# HackmodWear_workingcopy3.net
KiCad netlist of a schematic drawn in EAGLE
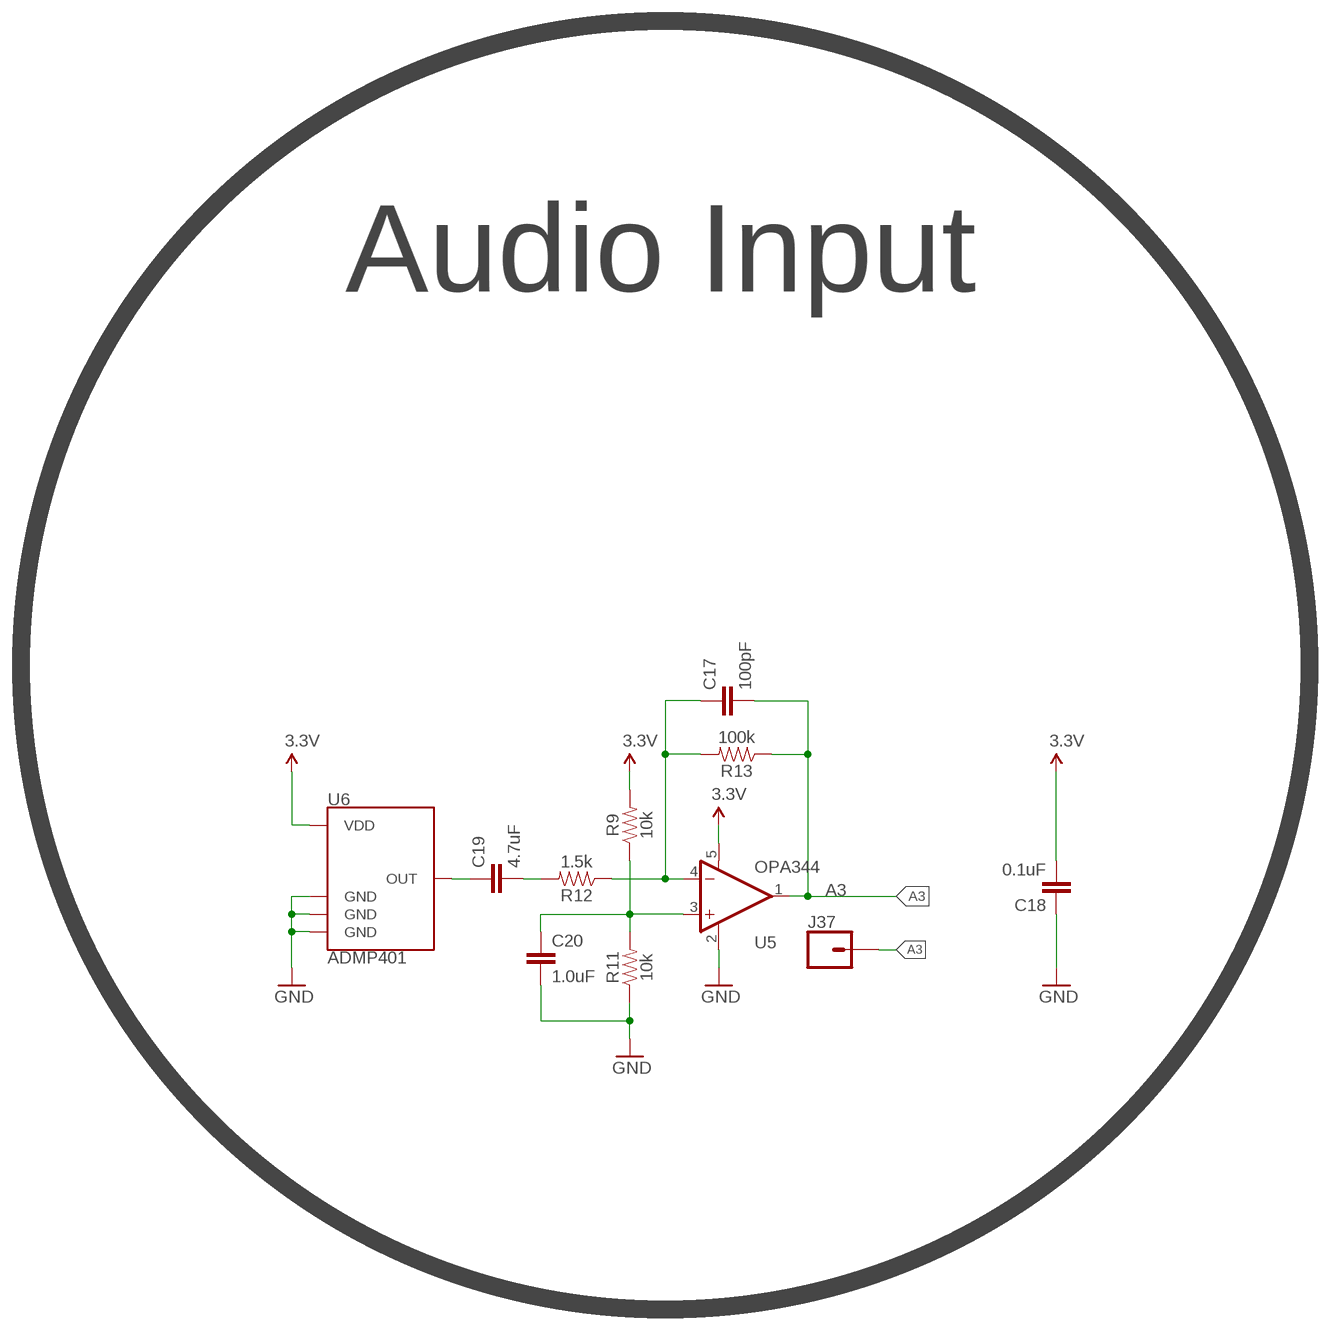
[diagram p0: schematic, sheet 1, part 1 of 3]
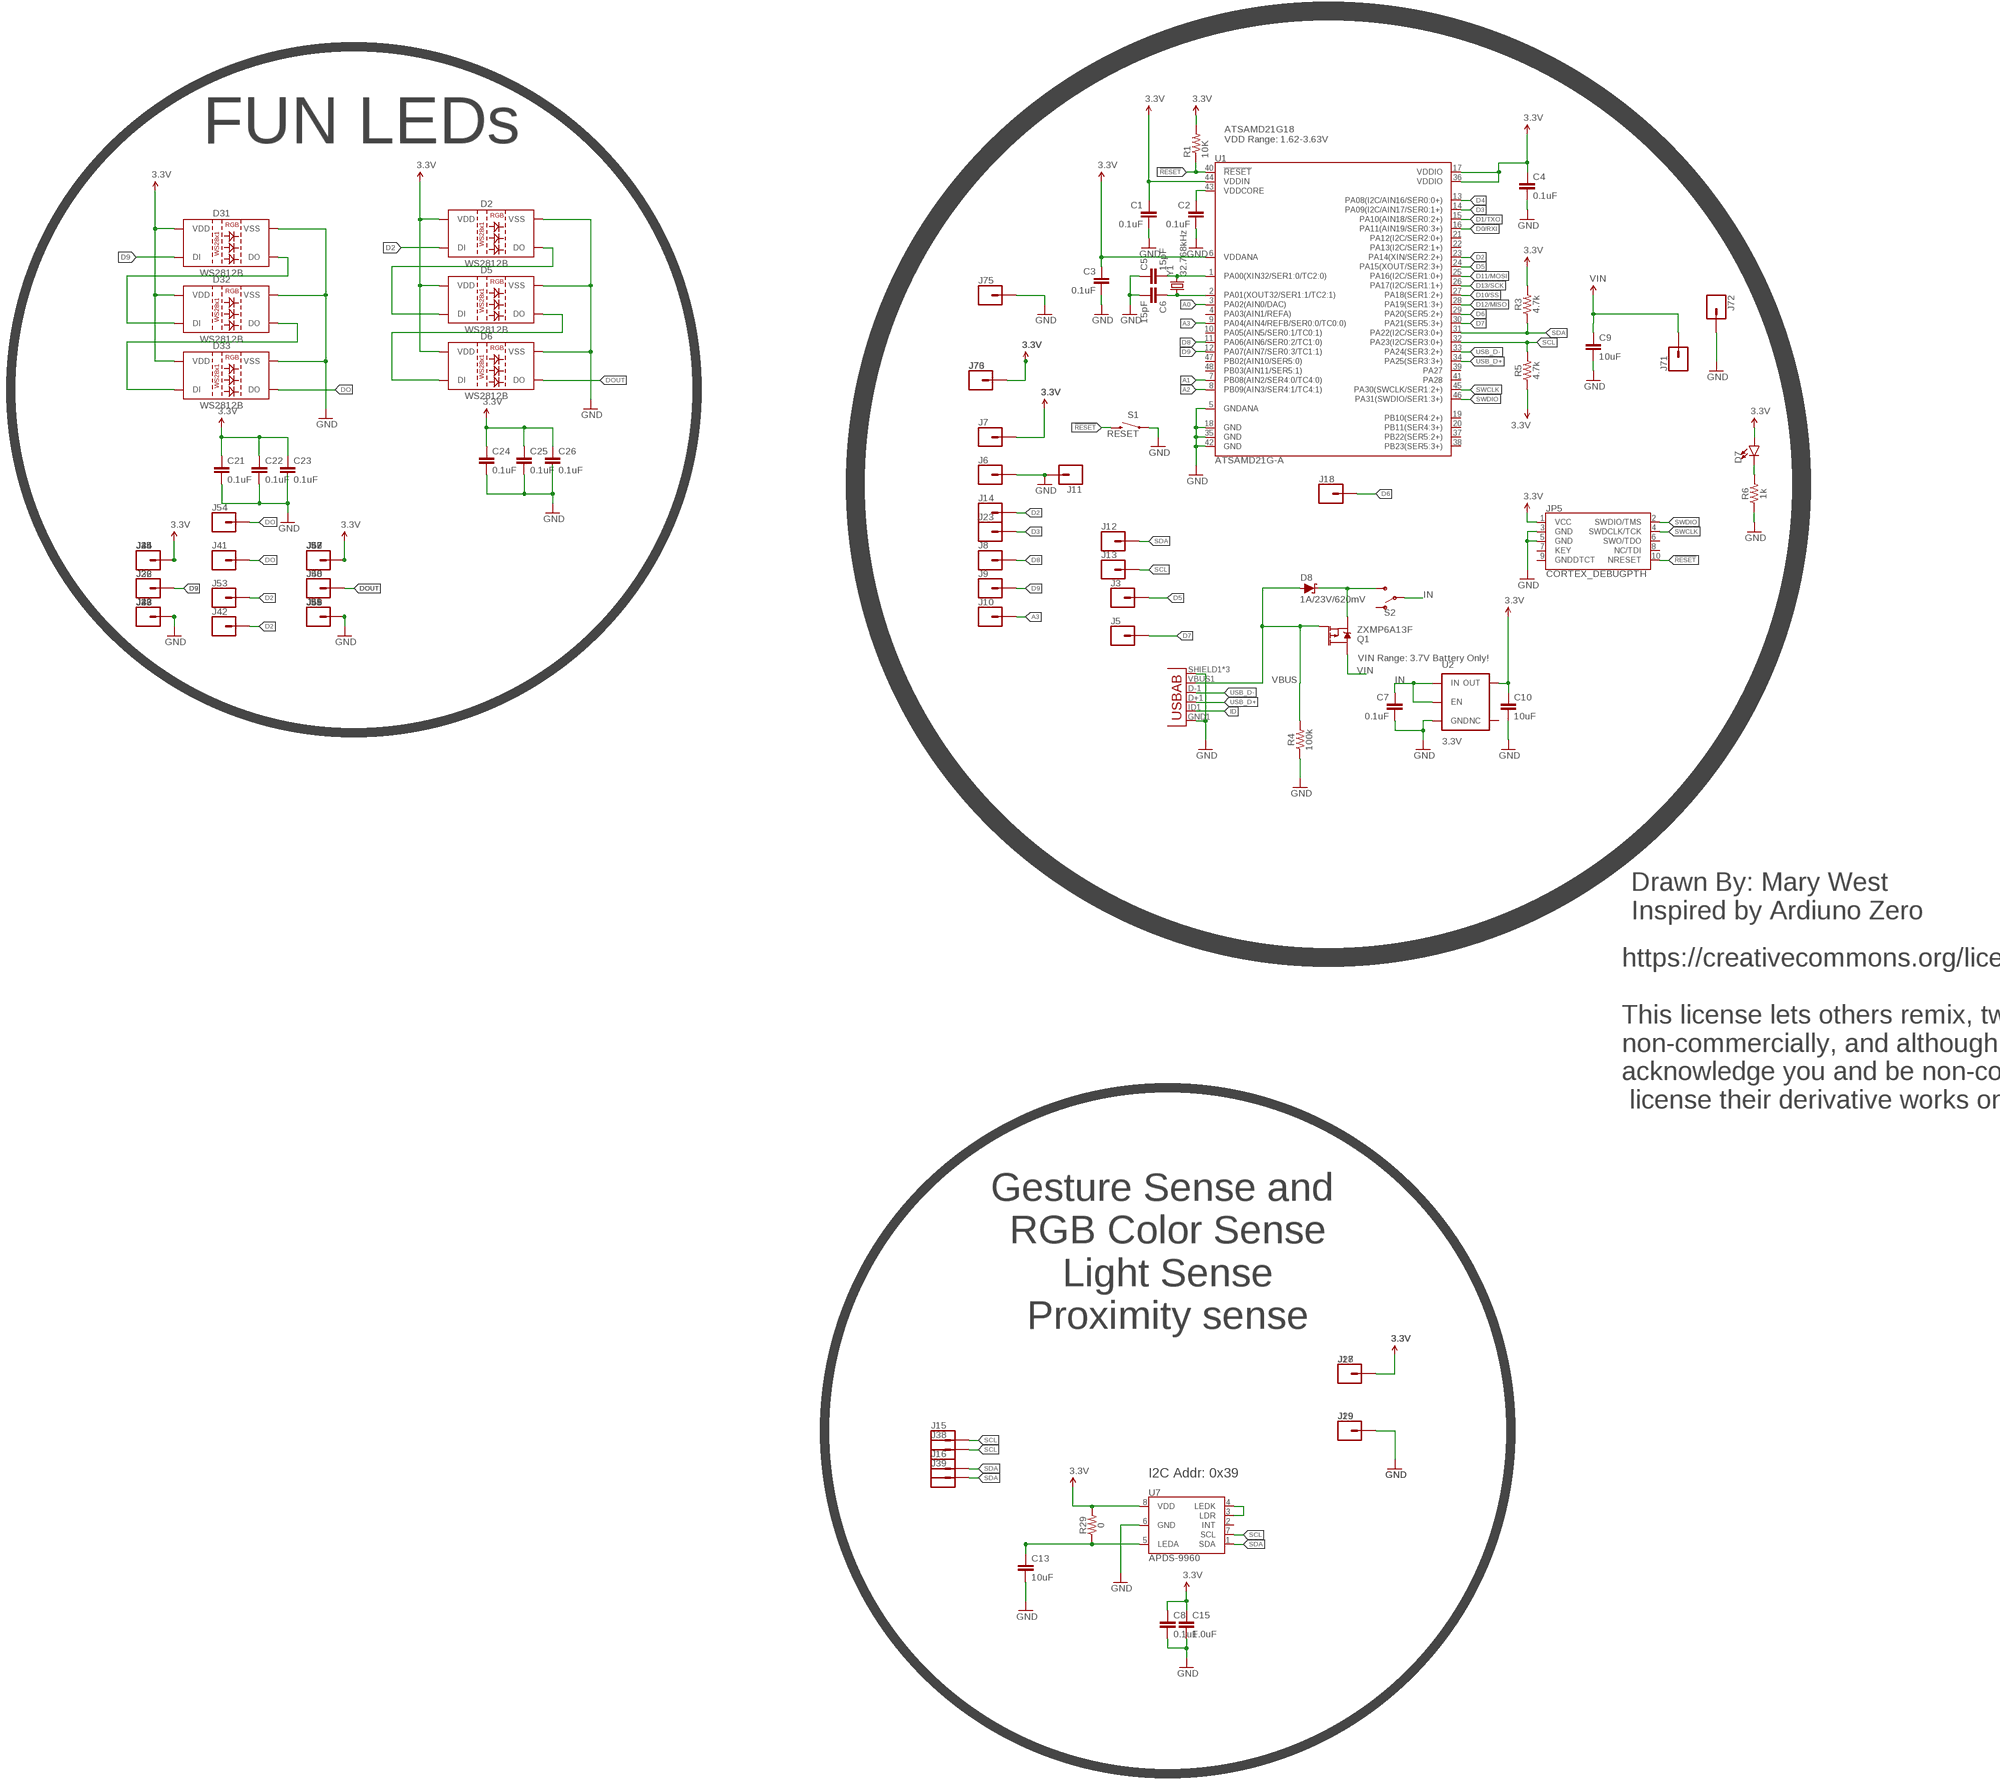
[diagram p1: schematic, sheet 1, part 2 of 3]
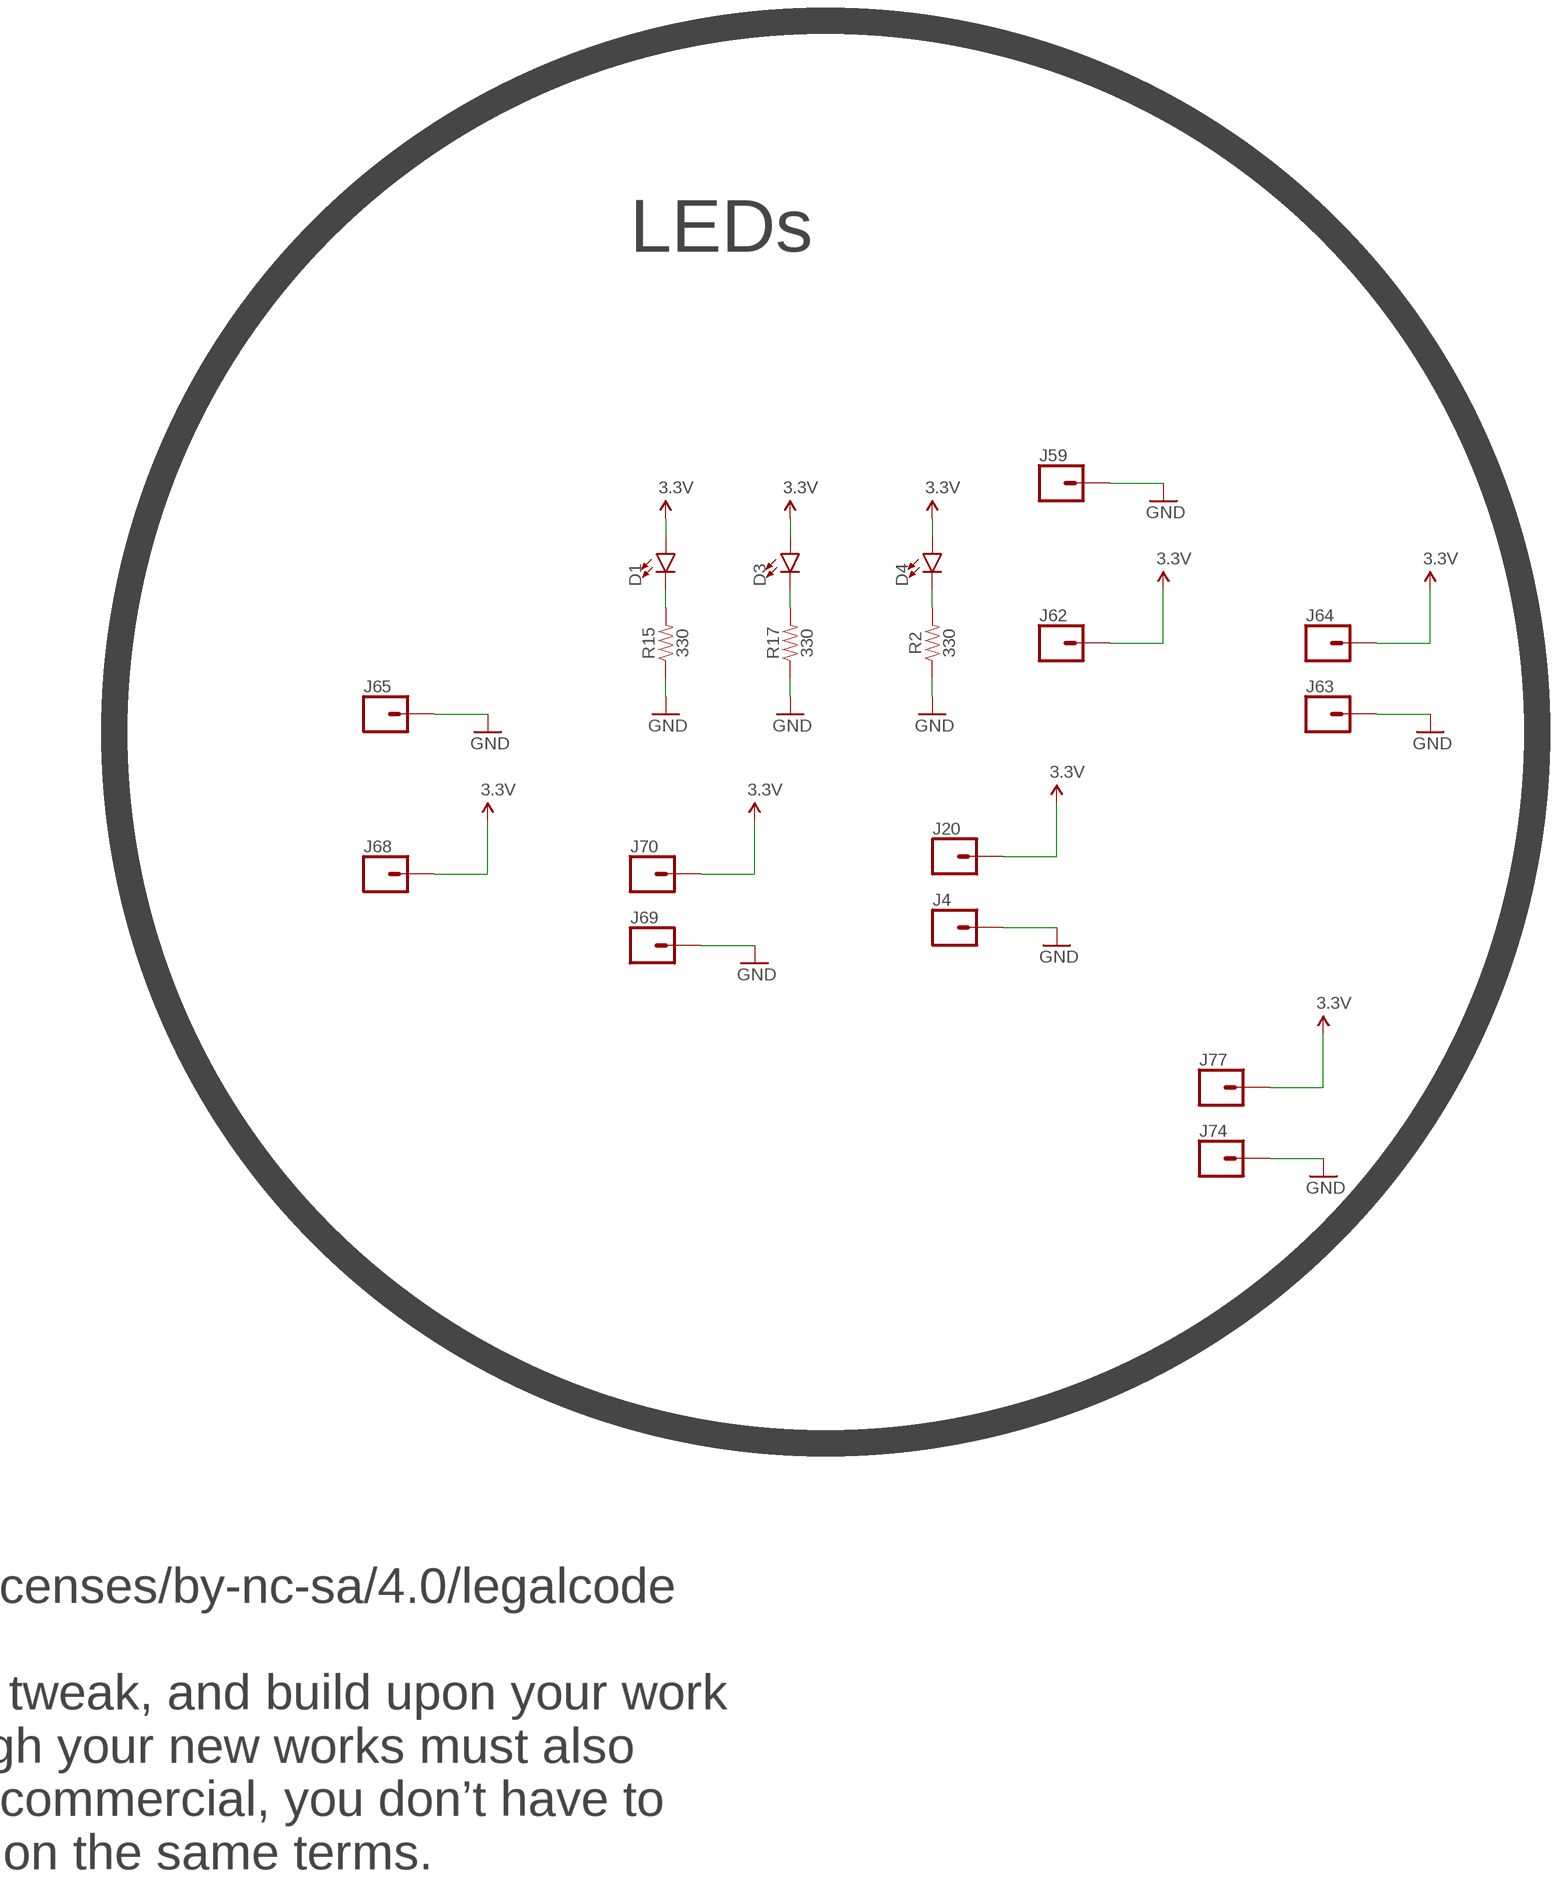
[diagram p2: schematic, sheet 1, part 3 of 3]

(export (version "E")
  (design (tool "Eeschema 10.0.6"))
  (components
    (comp (ref "C1")
      (value "0.1uF")
      (footprint "eagle-import:0603")
      (libsource (lib "eagle-import") (part "0.1UF-0603-25V-(+80/-20%)"))
    )
    (comp (ref "C2")
      (value "0.1uF")
      (footprint "eagle-import:0603")
      (libsource (lib "eagle-import") (part "0.1UF-0603-25V-(+80/-20%)"))
    )
    (comp (ref "C3")
      (value "0.1uF")
      (footprint "eagle-import:0603")
      (libsource (lib "eagle-import") (part "0.1UF-0603-25V-(+80/-20%)"))
    )
    (comp (ref "C4")
      (value "0.1uF")
      (footprint "eagle-import:0603")
      (libsource (lib "eagle-import") (part "0.1UF-0603-25V-(+80/-20%)"))
    )
    (comp (ref "C5")
      (value "15pF")
      (footprint "eagle-import:0603")
      (libsource (lib "eagle-import") (part "15PF-0603-50V-5%"))
    )
    (comp (ref "C6")
      (value "15pF")
      (footprint "eagle-import:0603")
      (libsource (lib "eagle-import") (part "15PF-0603-50V-5%"))
    )
    (comp (ref "C7")
      (value "0.1uF")
      (footprint "eagle-import:0603")
      (libsource (lib "eagle-import") (part "0.1UF-0603-25V-(+80/-20%)"))
    )
    (comp (ref "C8")
      (value "0.1uF")
      (footprint "eagle-import:0603")
      (libsource (lib "eagle-import") (part "0.1UF-0603-25V-(+80/-20%)"))
    )
    (comp (ref "C9")
      (value "10uF")
      (footprint "eagle-import:0603")
      (libsource (lib "eagle-import") (part "SparkFun-Capacitors_510_10UF-0603-6.3V-20%"))
    )
    (comp (ref "C10")
      (value "10uF")
      (footprint "eagle-import:0603")
      (libsource (lib "eagle-import") (part "SparkFun-Capacitors_510_10UF-0603-6.3V-20%"))
    )
    (comp (ref "C13")
      (value "10uF")
      (footprint "eagle-import:0805")
      (libsource (lib "eagle-import") (part "10UF-0805-10V-10%"))
    )
    (comp (ref "C15")
      (value "1.0uF")
      (footprint "eagle-import:0603")
      (libsource (lib "eagle-import") (part "1.0UF-0603-16V-10%"))
    )
    (comp (ref "C17")
      (value "100pF")
      (footprint "eagle-import:0603")
      (libsource (lib "eagle-import") (part "100PF-0603-50V-5%"))
    )
    (comp (ref "C18")
      (value "0.1uF")
      (footprint "eagle-import:0603")
      (libsource (lib "eagle-import") (part "0.1UF-0603-25V-(+80/-20%)"))
    )
    (comp (ref "C19")
      (value "4.7uF")
      (footprint "eagle-import:0603")
      (libsource (lib "eagle-import") (part "4.7UF-0603-6.3V-(10%)"))
    )
    (comp (ref "C20")
      (value "1.0uF")
      (footprint "eagle-import:0603")
      (libsource (lib "eagle-import") (part "1.0UF-0603-16V-10%"))
    )
    (comp (ref "C21")
      (value "0.1uF")
      (footprint "eagle-import:0603")
      (libsource (lib "eagle-import") (part "0.1UF-0603-25V-(+80/-20%)"))
    )
    (comp (ref "C22")
      (value "0.1uF")
      (footprint "eagle-import:0603")
      (libsource (lib "eagle-import") (part "0.1UF-0603-25V-(+80/-20%)"))
    )
    (comp (ref "C23")
      (value "0.1uF")
      (footprint "eagle-import:0603")
      (libsource (lib "eagle-import") (part "0.1UF-0603-25V-(+80/-20%)"))
    )
    (comp (ref "C24")
      (value "0.1uF")
      (footprint "eagle-import:0603")
      (libsource (lib "eagle-import") (part "0.1UF-0603-25V-(+80/-20%)"))
    )
    (comp (ref "C25")
      (value "0.1uF")
      (footprint "eagle-import:0603")
      (libsource (lib "eagle-import") (part "0.1UF-0603-25V-(+80/-20%)"))
    )
    (comp (ref "C26")
      (value "0.1uF")
      (footprint "eagle-import:0603")
      (libsource (lib "eagle-import") (part "0.1UF-0603-25V-(+80/-20%)"))
    )
    (comp (ref "D1")
      (value "LED1206")
      (footprint "eagle-import:LED-1206")
      (libsource (lib "eagle-import") (part "LED1206"))
    )
    (comp (ref "D2")
      (value "WS2812B")
      (footprint "eagle-import:WS2812B")
      (libsource (lib "eagle-import") (part "WS2812B"))
    )
    (comp (ref "D3")
      (value "LED1206")
      (footprint "eagle-import:LED-1206")
      (libsource (lib "eagle-import") (part "LED1206"))
    )
    (comp (ref "D4")
      (value "LED1206")
      (footprint "eagle-import:LED-1206")
      (libsource (lib "eagle-import") (part "LED1206"))
    )
    (comp (ref "D5")
      (value "WS2812B")
      (footprint "eagle-import:WS2812B")
      (libsource (lib "eagle-import") (part "WS2812B"))
    )
    (comp (ref "D6")
      (value "WS2812B")
      (footprint "eagle-import:WS2812B")
      (libsource (lib "eagle-import") (part "WS2812B"))
    )
    (comp (ref "D7")
      (value "LED1206")
      (footprint "eagle-import:LED-1206")
      (libsource (lib "eagle-import") (part "LED1206"))
    )
    (comp (ref "D8")
      (value "1A/23V/620mV")
      (footprint "eagle-import:SOD-323")
      (libsource (lib "eagle-import") (part "DIODE-SCHOTTKY-BAT20J"))
    )
    (comp (ref "D31")
      (value "WS2812B")
      (footprint "eagle-import:WS2812B")
      (libsource (lib "eagle-import") (part "WS2812B"))
    )
    (comp (ref "D32")
      (value "WS2812B")
      (footprint "eagle-import:WS2812B")
      (libsource (lib "eagle-import") (part "WS2812B"))
    )
    (comp (ref "D33")
      (value "WS2812B")
      (footprint "eagle-import:WS2812B")
      (libsource (lib "eagle-import") (part "WS2812B"))
    )
    (comp (ref "J3")
      (value "CONN_01")
      (footprint "eagle-import:1X01")
      (libsource (lib "eagle-import") (part "CONN_01"))
    )
    (comp (ref "J4")
      (value "CONN_01")
      (footprint "eagle-import:1X01")
      (libsource (lib "eagle-import") (part "CONN_01"))
    )
    (comp (ref "J5")
      (value "CONN_01")
      (footprint "eagle-import:1X01")
      (libsource (lib "eagle-import") (part "CONN_01"))
    )
    (comp (ref "J6")
      (value "CONN_01")
      (footprint "eagle-import:1X01")
      (libsource (lib "eagle-import") (part "CONN_01"))
    )
    (comp (ref "J7")
      (value "CONN_01")
      (footprint "eagle-import:1X01")
      (libsource (lib "eagle-import") (part "CONN_01"))
    )
    (comp (ref "J8")
      (value "CONN_01")
      (footprint "eagle-import:1X01")
      (libsource (lib "eagle-import") (part "CONN_01"))
    )
    (comp (ref "J9")
      (value "CONN_01")
      (footprint "eagle-import:1X01")
      (libsource (lib "eagle-import") (part "CONN_01"))
    )
    (comp (ref "J10")
      (value "CONN_01")
      (footprint "eagle-import:1X01")
      (libsource (lib "eagle-import") (part "CONN_01"))
    )
    (comp (ref "J11")
      (value "CONN_01")
      (footprint "eagle-import:1X01")
      (libsource (lib "eagle-import") (part "CONN_01"))
    )
    (comp (ref "J12")
      (value "CONN_01")
      (footprint "eagle-import:1X01")
      (libsource (lib "eagle-import") (part "CONN_01"))
    )
    (comp (ref "J13")
      (value "CONN_01")
      (footprint "eagle-import:1X01")
      (libsource (lib "eagle-import") (part "CONN_01"))
    )
    (comp (ref "J14")
      (value "CONN_01")
      (footprint "eagle-import:1X01")
      (libsource (lib "eagle-import") (part "CONN_01"))
    )
    (comp (ref "J15")
      (value "CONN_01")
      (footprint "eagle-import:1X01")
      (libsource (lib "eagle-import") (part "CONN_01"))
    )
    (comp (ref "J16")
      (value "CONN_01")
      (footprint "eagle-import:1X01")
      (libsource (lib "eagle-import") (part "CONN_01"))
    )
    (comp (ref "J17")
      (value "CONN_01")
      (footprint "eagle-import:1X01")
      (libsource (lib "eagle-import") (part "CONN_01"))
    )
    (comp (ref "J18")
      (value "CONN_01")
      (footprint "eagle-import:1X01")
      (libsource (lib "eagle-import") (part "CONN_01"))
    )
    (comp (ref "J19")
      (value "CONN_01")
      (footprint "eagle-import:1X01")
      (libsource (lib "eagle-import") (part "CONN_01"))
    )
    (comp (ref "J20")
      (value "CONN_01")
      (footprint "eagle-import:1X01")
      (libsource (lib "eagle-import") (part "CONN_01"))
    )
    (comp (ref "J23")
      (value "CONN_01")
      (footprint "eagle-import:1X01")
      (libsource (lib "eagle-import") (part "CONN_01"))
    )
    (comp (ref "J25")
      (value "CONN_01")
      (footprint "eagle-import:1X01")
      (libsource (lib "eagle-import") (part "CONN_01"))
    )
    (comp (ref "J26")
      (value "CONN_01")
      (footprint "eagle-import:1X01")
      (libsource (lib "eagle-import") (part "CONN_01"))
    )
    (comp (ref "J27")
      (value "CONN_01")
      (footprint "eagle-import:1X01")
      (libsource (lib "eagle-import") (part "CONN_01"))
    )
    (comp (ref "J28")
      (value "CONN_01")
      (footprint "eagle-import:1X01")
      (libsource (lib "eagle-import") (part "CONN_01"))
    )
    (comp (ref "J29")
      (value "CONN_01")
      (footprint "eagle-import:1X01")
      (libsource (lib "eagle-import") (part "CONN_01"))
    )
    (comp (ref "J32")
      (value "CONN_01")
      (footprint "eagle-import:1X01")
      (libsource (lib "eagle-import") (part "CONN_01"))
    )
    (comp (ref "J33")
      (value "CONN_01")
      (footprint "eagle-import:1X01")
      (libsource (lib "eagle-import") (part "CONN_01"))
    )
    (comp (ref "J34")
      (value "CONN_01")
      (footprint "eagle-import:1X01")
      (libsource (lib "eagle-import") (part "CONN_01"))
    )
    (comp (ref "J37")
      (value "CONN_01")
      (footprint "eagle-import:1X01")
      (libsource (lib "eagle-import") (part "CONN_01"))
    )
    (comp (ref "J38")
      (value "CONN_01")
      (footprint "eagle-import:1X01")
      (libsource (lib "eagle-import") (part "CONN_01"))
    )
    (comp (ref "J39")
      (value "CONN_01")
      (footprint "eagle-import:1X01")
      (libsource (lib "eagle-import") (part "CONN_01"))
    )
    (comp (ref "J41")
      (value "CONN_01")
      (footprint "eagle-import:1X01")
      (libsource (lib "eagle-import") (part "CONN_01"))
    )
    (comp (ref "J42")
      (value "CONN_01")
      (footprint "eagle-import:1X01")
      (libsource (lib "eagle-import") (part "CONN_01"))
    )
    (comp (ref "J43")
      (value "CONN_01")
      (footprint "eagle-import:1X01")
      (libsource (lib "eagle-import") (part "CONN_01"))
    )
    (comp (ref "J44")
      (value "CONN_01")
      (footprint "eagle-import:1X01")
      (libsource (lib "eagle-import") (part "CONN_01"))
    )
    (comp (ref "J45")
      (value "CONN_01")
      (footprint "eagle-import:1X01")
      (libsource (lib "eagle-import") (part "CONN_01"))
    )
    (comp (ref "J46")
      (value "CONN_01")
      (footprint "eagle-import:1X01")
      (libsource (lib "eagle-import") (part "CONN_01"))
    )
    (comp (ref "J47")
      (value "CONN_01")
      (footprint "eagle-import:1X01")
      (libsource (lib "eagle-import") (part "CONN_01"))
    )
    (comp (ref "J48")
      (value "CONN_01")
      (footprint "eagle-import:1X01")
      (libsource (lib "eagle-import") (part "CONN_01"))
    )
    (comp (ref "J49")
      (value "CONN_01")
      (footprint "eagle-import:1X01")
      (libsource (lib "eagle-import") (part "CONN_01"))
    )
    (comp (ref "J50")
      (value "CONN_01")
      (footprint "eagle-import:1X01")
      (libsource (lib "eagle-import") (part "CONN_01"))
    )
    (comp (ref "J51")
      (value "CONN_01")
      (footprint "eagle-import:1X01")
      (libsource (lib "eagle-import") (part "CONN_01"))
    )
    (comp (ref "J52")
      (value "CONN_01")
      (footprint "eagle-import:1X01")
      (libsource (lib "eagle-import") (part "CONN_01"))
    )
    (comp (ref "J53")
      (value "CONN_01")
      (footprint "eagle-import:1X01")
      (libsource (lib "eagle-import") (part "CONN_01"))
    )
    (comp (ref "J54")
      (value "CONN_01")
      (footprint "eagle-import:1X01")
      (libsource (lib "eagle-import") (part "CONN_01"))
    )
    (comp (ref "J55")
      (value "CONN_01")
      (footprint "eagle-import:1X01")
      (libsource (lib "eagle-import") (part "CONN_01"))
    )
    (comp (ref "J56")
      (value "CONN_01")
      (footprint "eagle-import:1X01")
      (libsource (lib "eagle-import") (part "CONN_01"))
    )
    (comp (ref "J57")
      (value "CONN_01")
      (footprint "eagle-import:1X01")
      (libsource (lib "eagle-import") (part "CONN_01"))
    )
    (comp (ref "J58")
      (value "CONN_01")
      (footprint "eagle-import:1X01")
      (libsource (lib "eagle-import") (part "CONN_01"))
    )
    (comp (ref "J59")
      (value "CONN_01")
      (footprint "eagle-import:1X01")
      (libsource (lib "eagle-import") (part "CONN_01"))
    )
    (comp (ref "J62")
      (value "CONN_01")
      (footprint "eagle-import:1X01")
      (libsource (lib "eagle-import") (part "CONN_01"))
    )
    (comp (ref "J63")
      (value "CONN_01")
      (footprint "eagle-import:1X01")
      (libsource (lib "eagle-import") (part "CONN_01"))
    )
    (comp (ref "J64")
      (value "CONN_01")
      (footprint "eagle-import:1X01")
      (libsource (lib "eagle-import") (part "CONN_01"))
    )
    (comp (ref "J65")
      (value "CONN_01")
      (footprint "eagle-import:1X01")
      (libsource (lib "eagle-import") (part "CONN_01"))
    )
    (comp (ref "J68")
      (value "CONN_01")
      (footprint "eagle-import:1X01")
      (libsource (lib "eagle-import") (part "CONN_01"))
    )
    (comp (ref "J69")
      (value "CONN_01")
      (footprint "eagle-import:1X01")
      (libsource (lib "eagle-import") (part "CONN_01"))
    )
    (comp (ref "J70")
      (value "CONN_01")
      (footprint "eagle-import:1X01")
      (libsource (lib "eagle-import") (part "CONN_01"))
    )
    (comp (ref "J71")
      (value "CONN_01")
      (footprint "eagle-import:1X01")
      (libsource (lib "eagle-import") (part "CONN_01"))
    )
    (comp (ref "J72")
      (value "CONN_01")
      (footprint "eagle-import:1X01")
      (libsource (lib "eagle-import") (part "CONN_01"))
    )
    (comp (ref "J73")
      (value "CONN_01")
      (footprint "eagle-import:1X01")
      (libsource (lib "eagle-import") (part "CONN_01"))
    )
    (comp (ref "J74")
      (value "CONN_01")
      (footprint "eagle-import:1X01")
      (libsource (lib "eagle-import") (part "CONN_01"))
    )
    (comp (ref "J75")
      (value "CONN_01")
      (footprint "eagle-import:1X01")
      (libsource (lib "eagle-import") (part "CONN_01"))
    )
    (comp (ref "J76")
      (value "CONN_01")
      (footprint "eagle-import:1X01")
      (libsource (lib "eagle-import") (part "CONN_01"))
    )
    (comp (ref "J77")
      (value "CONN_01")
      (footprint "eagle-import:1X01")
      (libsource (lib "eagle-import") (part "CONN_01"))
    )
    (comp (ref "JP3")
      (value "USB-ABCONN-11794")
      (footprint "eagle-import:USB-AB-MICRO-SMD_V03")
      (libsource (lib "eagle-import") (part "USB-ABCONN-11794"))
    )
    (comp (ref "JP5")
      (value "CORTEX_DEBUGPTH")
      (footprint "eagle-import:2X5-PTH-1.27MM")
      (libsource (lib "eagle-import") (part "CORTEX_DEBUGPTH"))
    )
    (comp (ref "Q1")
      (value "ZXMP6A13F")
      (footprint "eagle-import:SOT23-3")
      (libsource (lib "eagle-import") (part "MOSFET_PCH-SI2309DS"))
    )
    (comp (ref "R1")
      (value "10K")
      (footprint "eagle-import:0603-RES@1")
      (libsource (lib "eagle-import") (part "10KOHM-1/10W-1%(0603)0603"))
    )
    (comp (ref "R2")
      (value "330")
      (footprint "eagle-import:0603")
      (libsource (lib "eagle-import") (part "330OHM-0603-1/10W-1%"))
    )
    (comp (ref "R3")
      (value "4.7k")
      (footprint "eagle-import:0603")
      (libsource (lib "eagle-import") (part "4.7KOHM-0603-1/10W-1%"))
    )
    (comp (ref "R4")
      (value "100k")
      (footprint "eagle-import:0603")
      (libsource (lib "eagle-import") (part "SparkFun-Resistors_532_100KOHM-0603-1/10W-1%"))
    )
    (comp (ref "R5")
      (value "4.7k")
      (footprint "eagle-import:0603")
      (libsource (lib "eagle-import") (part "4.7KOHM-0603-1/10W-1%"))
    )
    (comp (ref "R6")
      (value "1k")
      (footprint "eagle-import:0603")
      (libsource (lib "eagle-import") (part "330OHM-0603-1/10W-1%"))
    )
    (comp (ref "R9")
      (value "10k")
      (footprint "eagle-import:0603")
      (libsource (lib "eagle-import") (part "10KOHM-0603-1/10W-1%"))
    )
    (comp (ref "R11")
      (value "10k")
      (footprint "eagle-import:0603")
      (libsource (lib "eagle-import") (part "10KOHM-0603-1/10W-1%"))
    )
    (comp (ref "R12")
      (value "1.5k")
      (footprint "eagle-import:0603")
      (libsource (lib "eagle-import") (part "1.5KOHM-0603-1/10W-1%"))
    )
    (comp (ref "R13")
      (value "100k")
      (footprint "eagle-import:0603")
      (libsource (lib "eagle-import") (part "100KOHM-0603-1/10W-1%"))
    )
    (comp (ref "R15")
      (value "330")
      (footprint "eagle-import:0603")
      (libsource (lib "eagle-import") (part "330OHM-0603-1/10W-1%"))
    )
    (comp (ref "R17")
      (value "330")
      (footprint "eagle-import:0603")
      (libsource (lib "eagle-import") (part "330OHM-0603-1/10W-1%"))
    )
    (comp (ref "R29")
      (value "0")
      (footprint "eagle-import:0603")
      (libsource (lib "eagle-import") (part "0OHM-0603-1/10W-5%"))
    )
    (comp (ref "S1")
      (value "RESET")
      (footprint "eagle-import:TACTILE_SWITCH_SMD_4.6X2.8MM")
      (libsource (lib "eagle-import") (part "SWITCH-MOMENTARY-2SMD-4.6X2.8MM"))
    )
    (comp (ref "S2")
      (value "SWITCH-SPDT-SMD-AYZ0202")
      (footprint "eagle-import:SWITCH_DPDT_SMD_AYZ0202")
      (libsource (lib "eagle-import") (part "SWITCH-SPDT-SMD-AYZ0202"))
    )
    (comp (ref "U1")
      (value "ATSAMD21G-A")
      (footprint "eagle-import:TQFP-48")
      (libsource (lib "eagle-import") (part "ATSAMD21G-A"))
    )
    (comp (ref "U2")
      (value "3.3V")
      (footprint "eagle-import:SOT23-5")
      (libsource (lib "eagle-import") (part "V_REG_AP2112K-3.3V"))
    )
    (comp (ref "U5")
      (value "OPA344")
      (footprint "eagle-import:SOT23-5")
      (libsource (lib "eagle-import") (part "OPA344"))
    )
    (comp (ref "U6")
      (value "ADMP401")
      (footprint "eagle-import:ADMP401")
      (libsource (lib "eagle-import") (part "ADMP401"))
    )
    (comp (ref "U7")
      (value "APDS-9960")
      (footprint "eagle-import:APDS-9960")
      (libsource (lib "eagle-import") (part "APDS-9960"))
    )
    (comp (ref "Y1")
      (value "32.768kHz")
      (footprint "eagle-import:CRYSTAL-SMD-3.2X1.5MM")
      (libsource (lib "eagle-import") (part "CRYSTAL3.2X1.5MM"))
    )
  )
  (nets
    (net (code "1") (name "/IN") (class "Default")
      (node (ref "C7") (pin "1") (pinfunction "1_1") (pintype "passive"))
      (node (ref "S2") (pin "2") (pinfunction "P_2") (pintype "passive"))
      (node (ref "U2") (pin "1") (pinfunction "IN_1") (pintype "input"))
      (node (ref "U2") (pin "3") (pinfunction "EN_3") (pintype "input"))
    )
    (net (code "2") (name "/VBUS") (class "Default")
      (node (ref "D8") (pin "A") (pinfunction "A_A") (pintype "passive"))
      (node (ref "JP3") (pin "VBUS1") (pinfunction "VBUS_VBUS1") (pintype "bidirectional"))
      (node (ref "Q1") (pin "1") (pinfunction "G_1") (pintype "bidirectional"))
      (node (ref "R4") (pin "2") (pinfunction "2_2") (pintype "passive"))
    )
    (net (code "3") (name "/~{RESET}") (class "Default")
      (node (ref "JP5") (pin "10") (pinfunction "NRESET_10") (pintype "bidirectional"))
      (node (ref "R1") (pin "1") (pinfunction "1_1") (pintype "passive"))
      (node (ref "S1") (pin "3") (pinfunction "2_3") (pintype "passive"))
      (node (ref "S1") (pin "4") (pinfunction "2_4") (pintype "passive"))
      (node (ref "U1") (pin "40") (pinfunction "~{RESET}_40") (pintype "bidirectional"))
    )
    (net (code "4") (name "3.3V") (class "Default")
      (node (ref "C1") (pin "1") (pinfunction "1_1") (pintype "passive"))
      (node (ref "C10") (pin "1") (pinfunction "1_1") (pintype "passive"))
      (node (ref "C15") (pin "1") (pinfunction "1_1") (pintype "passive"))
      (node (ref "C18") (pin "2") (pinfunction "2_2") (pintype "passive"))
      (node (ref "C21") (pin "1") (pinfunction "1_1") (pintype "passive"))
      (node (ref "C22") (pin "1") (pinfunction "1_1") (pintype "passive"))
      (node (ref "C23") (pin "1") (pinfunction "1_1") (pintype "passive"))
      (node (ref "C24") (pin "1") (pinfunction "1_1") (pintype "passive"))
      (node (ref "C25") (pin "1") (pinfunction "1_1") (pintype "passive"))
      (node (ref "C26") (pin "1") (pinfunction "1_1") (pintype "passive"))
      (node (ref "C3") (pin "1") (pinfunction "1_1") (pintype "passive"))
      (node (ref "C4") (pin "1") (pinfunction "1_1") (pintype "passive"))
      (node (ref "C8") (pin "1") (pinfunction "1_1") (pintype "passive"))
      (node (ref "D1") (pin "A") (pinfunction "A_A") (pintype "passive"))
      (node (ref "D2") (pin "1") (pinfunction "VDD_1") (pintype "bidirectional"))
      (node (ref "D3") (pin "A") (pinfunction "A_A") (pintype "passive"))
      (node (ref "D31") (pin "1") (pinfunction "VDD_1") (pintype "bidirectional"))
      (node (ref "D32") (pin "1") (pinfunction "VDD_1") (pintype "bidirectional"))
      (node (ref "D33") (pin "1") (pinfunction "VDD_1") (pintype "bidirectional"))
      (node (ref "D4") (pin "A") (pinfunction "A_A") (pintype "passive"))
      (node (ref "D5") (pin "1") (pinfunction "VDD_1") (pintype "bidirectional"))
      (node (ref "D6") (pin "1") (pinfunction "VDD_1") (pintype "bidirectional"))
      (node (ref "D7") (pin "A") (pinfunction "A_A") (pintype "passive"))
      (node (ref "J17") (pin "P$1") (pinfunction "1_P$1") (pintype "passive"))
      (node (ref "J20") (pin "P$1") (pinfunction "1_P$1") (pintype "passive"))
      (node (ref "J25") (pin "P$1") (pinfunction "1_P$1") (pintype "passive"))
      (node (ref "J28") (pin "P$1") (pinfunction "1_P$1") (pintype "passive"))
      (node (ref "J34") (pin "P$1") (pinfunction "1_P$1") (pintype "passive"))
      (node (ref "J44") (pin "P$1") (pinfunction "1_P$1") (pintype "passive"))
      (node (ref "J45") (pin "P$1") (pinfunction "1_P$1") (pintype "passive"))
      (node (ref "J47") (pin "P$1") (pinfunction "1_P$1") (pintype "passive"))
      (node (ref "J52") (pin "P$1") (pinfunction "1_P$1") (pintype "passive"))
      (node (ref "J56") (pin "P$1") (pinfunction "1_P$1") (pintype "passive"))
      (node (ref "J57") (pin "P$1") (pinfunction "1_P$1") (pintype "passive"))
      (node (ref "J62") (pin "P$1") (pinfunction "1_P$1") (pintype "passive"))
      (node (ref "J64") (pin "P$1") (pinfunction "1_P$1") (pintype "passive"))
      (node (ref "J68") (pin "P$1") (pinfunction "1_P$1") (pintype "passive"))
      (node (ref "J7") (pin "P$1") (pinfunction "1_P$1") (pintype "passive"))
      (node (ref "J70") (pin "P$1") (pinfunction "1_P$1") (pintype "passive"))
      (node (ref "J73") (pin "P$1") (pinfunction "1_P$1") (pintype "passive"))
      (node (ref "J76") (pin "P$1") (pinfunction "1_P$1") (pintype "passive"))
      (node (ref "J77") (pin "P$1") (pinfunction "1_P$1") (pintype "passive"))
      (node (ref "JP5") (pin "1") (pinfunction "VCC_1") (pintype "bidirectional"))
      (node (ref "R1") (pin "2") (pinfunction "2_2") (pintype "passive"))
      (node (ref "R29") (pin "2") (pinfunction "2_2") (pintype "passive"))
      (node (ref "R3") (pin "2") (pinfunction "2_2") (pintype "passive"))
      (node (ref "R5") (pin "1") (pinfunction "1_1") (pintype "passive"))
      (node (ref "R9") (pin "2") (pinfunction "2_2") (pintype "passive"))
      (node (ref "U1") (pin "17") (pinfunction "VDDIO_17") (pintype "bidirectional"))
      (node (ref "U1") (pin "36") (pinfunction "VDDIO_36") (pintype "bidirectional"))
      (node (ref "U1") (pin "44") (pinfunction "VDDIN_44") (pintype "bidirectional"))
      (node (ref "U1") (pin "6") (pinfunction "VDDANA_6") (pintype "bidirectional"))
      (node (ref "U2") (pin "5") (pinfunction "OUT_5") (pintype "passive"))
      (node (ref "U5") (pin "5") (pinfunction "V+_5") (pintype "power_in"))
      (node (ref "U6") (pin "5") (pinfunction "VDD_5") (pintype "bidirectional"))
      (node (ref "U7") (pin "8") (pinfunction "VDD_8") (pintype "bidirectional"))
    )
    (net (code "5") (name "A0") (class "Default")
      (node (ref "U1") (pin "3") (pinfunction "PA02(AIN0/DAC)_3") (pintype "bidirectional"))
    )
    (net (code "6") (name "A1") (class "Default")
      (node (ref "U1") (pin "7") (pinfunction "PB08(AIN2/SER4:0/TC4:0)_7") (pintype "bidirectional"))
    )
    (net (code "7") (name "A2") (class "Default")
      (node (ref "U1") (pin "8") (pinfunction "PB09(AIN3/SER4:1/TC4:1)_8") (pintype "bidirectional"))
    )
    (net (code "8") (name "A3") (class "Default")
      (node (ref "C17") (pin "2") (pinfunction "2_2") (pintype "passive"))
      (node (ref "J10") (pin "P$1") (pinfunction "1_P$1") (pintype "passive"))
      (node (ref "J37") (pin "P$1") (pinfunction "1_P$1") (pintype "passive"))
      (node (ref "R13") (pin "1") (pinfunction "1_1") (pintype "passive"))
      (node (ref "U1") (pin "9") (pinfunction "PA04(AIN4/REFB/SER0:0/TC0:0)_9") (pintype "bidirectional"))
      (node (ref "U5") (pin "1") (pinfunction "OUT_1") (pintype "output"))
    )
    (net (code "9") (name "D0{slash}RXI") (class "Default")
      (node (ref "U1") (pin "16") (pinfunction "PA11(AIN19/SER0:3+)_16") (pintype "bidirectional"))
    )
    (net (code "10") (name "D1{slash}TXO") (class "Default")
      (node (ref "U1") (pin "15") (pinfunction "PA10(AIN18/SER0:2+)_15") (pintype "bidirectional"))
    )
    (net (code "11") (name "D2") (class "Default")
      (node (ref "D2") (pin "4") (pinfunction "DI_4") (pintype "bidirectional"))
      (node (ref "J14") (pin "P$1") (pinfunction "1_P$1") (pintype "passive"))
      (node (ref "J42") (pin "P$1") (pinfunction "1_P$1") (pintype "passive"))
      (node (ref "J53") (pin "P$1") (pinfunction "1_P$1") (pintype "passive"))
      (node (ref "U1") (pin "23") (pinfunction "PA14(XIN/SER2:2+)_23") (pintype "bidirectional"))
    )
    (net (code "12") (name "D3") (class "Default")
      (node (ref "J23") (pin "P$1") (pinfunction "1_P$1") (pintype "passive"))
      (node (ref "U1") (pin "14") (pinfunction "PA09(I2C/AIN17/SER0:1+)_14") (pintype "bidirectional"))
    )
    (net (code "13") (name "D4") (class "Default")
      (node (ref "U1") (pin "13") (pinfunction "PA08(I2C/AIN16/SER0:0+)_13") (pintype "bidirectional"))
    )
    (net (code "14") (name "D5") (class "Default")
      (node (ref "J3") (pin "P$1") (pinfunction "1_P$1") (pintype "passive"))
      (node (ref "U1") (pin "24") (pinfunction "PA15(XOUT/SER2:3+)_24") (pintype "bidirectional"))
    )
    (net (code "15") (name "D6") (class "Default")
      (node (ref "J18") (pin "P$1") (pinfunction "1_P$1") (pintype "passive"))
      (node (ref "U1") (pin "29") (pinfunction "PA20(SER5:2+)_29") (pintype "bidirectional"))
    )
    (net (code "16") (name "D7") (class "Default")
      (node (ref "J5") (pin "P$1") (pinfunction "1_P$1") (pintype "passive"))
      (node (ref "U1") (pin "30") (pinfunction "PA21(SER5:3+)_30") (pintype "bidirectional"))
    )
    (net (code "17") (name "D8") (class "Default")
      (node (ref "J8") (pin "P$1") (pinfunction "1_P$1") (pintype "passive"))
      (node (ref "U1") (pin "11") (pinfunction "PA06(AIN6/SER0:2/TC1:0)_11") (pintype "bidirectional"))
    )
    (net (code "18") (name "D9") (class "Default")
      (node (ref "D31") (pin "4") (pinfunction "DI_4") (pintype "bidirectional"))
      (node (ref "J26") (pin "P$1") (pinfunction "1_P$1") (pintype "passive"))
      (node (ref "J32") (pin "P$1") (pinfunction "1_P$1") (pintype "passive"))
      (node (ref "J9") (pin "P$1") (pinfunction "1_P$1") (pintype "passive"))
      (node (ref "U1") (pin "12") (pinfunction "PA07(AIN7/SER0:3/TC1:1)_12") (pintype "bidirectional"))
    )
    (net (code "19") (name "D10{slash}SS") (class "Default")
      (node (ref "U1") (pin "27") (pinfunction "PA18(SER1:2+)_27") (pintype "bidirectional"))
    )
    (net (code "20") (name "D11{slash}MOSI") (class "Default")
      (node (ref "U1") (pin "25") (pinfunction "PA16(I2C/SER1:0+)_25") (pintype "bidirectional"))
    )
    (net (code "21") (name "D12{slash}MISO") (class "Default")
      (node (ref "U1") (pin "28") (pinfunction "PA19(SER1:3+)_28") (pintype "bidirectional"))
    )
    (net (code "22") (name "D13{slash}SCK") (class "Default")
      (node (ref "U1") (pin "26") (pinfunction "PA17(I2C/SER1:1+)_26") (pintype "bidirectional"))
    )
    (net (code "23") (name "DO") (class "Default")
      (node (ref "D33") (pin "2") (pinfunction "DO_2") (pintype "bidirectional"))
      (node (ref "J41") (pin "P$1") (pinfunction "1_P$1") (pintype "passive"))
      (node (ref "J54") (pin "P$1") (pinfunction "1_P$1") (pintype "passive"))
    )
    (net (code "24") (name "DOUT") (class "Default")
      (node (ref "D6") (pin "2") (pinfunction "DO_2") (pintype "bidirectional"))
      (node (ref "J48") (pin "P$1") (pinfunction "1_P$1") (pintype "passive"))
      (node (ref "J50") (pin "P$1") (pinfunction "1_P$1") (pintype "passive"))
    )
    (net (code "25") (name "GND") (class "Default")
      (node (ref "C1") (pin "2") (pinfunction "2_2") (pintype "passive"))
      (node (ref "C10") (pin "2") (pinfunction "2_2") (pintype "passive"))
      (node (ref "C13") (pin "2") (pinfunction "2_2") (pintype "passive"))
      (node (ref "C15") (pin "2") (pinfunction "2_2") (pintype "passive"))
      (node (ref "C18") (pin "1") (pinfunction "1_1") (pintype "passive"))
      (node (ref "C2") (pin "2") (pinfunction "2_2") (pintype "passive"))
      (node (ref "C20") (pin "2") (pinfunction "2_2") (pintype "passive"))
      (node (ref "C21") (pin "2") (pinfunction "2_2") (pintype "passive"))
      (node (ref "C22") (pin "2") (pinfunction "2_2") (pintype "passive"))
      (node (ref "C23") (pin "2") (pinfunction "2_2") (pintype "passive"))
      (node (ref "C24") (pin "2") (pinfunction "2_2") (pintype "passive"))
      (node (ref "C25") (pin "2") (pinfunction "2_2") (pintype "passive"))
      (node (ref "C26") (pin "2") (pinfunction "2_2") (pintype "passive"))
      (node (ref "C3") (pin "2") (pinfunction "2_2") (pintype "passive"))
      (node (ref "C4") (pin "2") (pinfunction "2_2") (pintype "passive"))
      (node (ref "C5") (pin "1") (pinfunction "1_1") (pintype "passive"))
      (node (ref "C6") (pin "2") (pinfunction "2_2") (pintype "passive"))
      (node (ref "C7") (pin "2") (pinfunction "2_2") (pintype "passive"))
      (node (ref "C8") (pin "2") (pinfunction "2_2") (pintype "passive"))
      (node (ref "C9") (pin "2") (pinfunction "2_2") (pintype "passive"))
      (node (ref "D2") (pin "3") (pinfunction "VSS_3") (pintype "bidirectional"))
      (node (ref "D31") (pin "3") (pinfunction "VSS_3") (pintype "bidirectional"))
      (node (ref "D32") (pin "3") (pinfunction "VSS_3") (pintype "bidirectional"))
      (node (ref "D33") (pin "3") (pinfunction "VSS_3") (pintype "bidirectional"))
      (node (ref "D5") (pin "3") (pinfunction "VSS_3") (pintype "bidirectional"))
      (node (ref "D6") (pin "3") (pinfunction "VSS_3") (pintype "bidirectional"))
      (node (ref "J11") (pin "P$1") (pinfunction "1_P$1") (pintype "passive"))
      (node (ref "J19") (pin "P$1") (pinfunction "1_P$1") (pintype "passive"))
      (node (ref "J27") (pin "P$1") (pinfunction "1_P$1") (pintype "passive"))
      (node (ref "J29") (pin "P$1") (pinfunction "1_P$1") (pintype "passive"))
      (node (ref "J33") (pin "P$1") (pinfunction "1_P$1") (pintype "passive"))
      (node (ref "J4") (pin "P$1") (pinfunction "1_P$1") (pintype "passive"))
      (node (ref "J43") (pin "P$1") (pinfunction "1_P$1") (pintype "passive"))
      (node (ref "J46") (pin "P$1") (pinfunction "1_P$1") (pintype "passive"))
      (node (ref "J49") (pin "P$1") (pinfunction "1_P$1") (pintype "passive"))
      (node (ref "J51") (pin "P$1") (pinfunction "1_P$1") (pintype "passive"))
      (node (ref "J55") (pin "P$1") (pinfunction "1_P$1") (pintype "passive"))
      (node (ref "J58") (pin "P$1") (pinfunction "1_P$1") (pintype "passive"))
      (node (ref "J59") (pin "P$1") (pinfunction "1_P$1") (pintype "passive"))
      (node (ref "J6") (pin "P$1") (pinfunction "1_P$1") (pintype "passive"))
      (node (ref "J63") (pin "P$1") (pinfunction "1_P$1") (pintype "passive"))
      (node (ref "J65") (pin "P$1") (pinfunction "1_P$1") (pintype "passive"))
      (node (ref "J69") (pin "P$1") (pinfunction "1_P$1") (pintype "passive"))
      (node (ref "J72") (pin "P$1") (pinfunction "1_P$1") (pintype "passive"))
      (node (ref "J74") (pin "P$1") (pinfunction "1_P$1") (pintype "passive"))
      (node (ref "J75") (pin "P$1") (pinfunction "1_P$1") (pintype "passive"))
      (node (ref "JP3") (pin "GND1") (pinfunction "GND_GND1") (pintype "bidirectional"))
      (node (ref "JP3") (pin "SHIELD1") (pinfunction "SHIELD_SHIELD1") (pintype "bidirectional"))
      (node (ref "JP3") (pin "SHIELD2") (pinfunction "SHIELD_SHIELD2") (pintype "bidirectional"))
      (node (ref "JP3") (pin "SHIELD3") (pinfunction "SHIELD_SHIELD3") (pintype "bidirectional"))
      (node (ref "JP5") (pin "3") (pinfunction "GND_3") (pintype "bidirectional"))
      (node (ref "JP5") (pin "5") (pinfunction "GND_5") (pintype "bidirectional"))
      (node (ref "R11") (pin "1") (pinfunction "1_1") (pintype "passive"))
      (node (ref "R15") (pin "1") (pinfunction "1_1") (pintype "passive"))
      (node (ref "R17") (pin "1") (pinfunction "1_1") (pintype "passive"))
      (node (ref "R2") (pin "1") (pinfunction "1_1") (pintype "passive"))
      (node (ref "R4") (pin "1") (pinfunction "1_1") (pintype "passive"))
      (node (ref "R6") (pin "1") (pinfunction "1_1") (pintype "passive"))
      (node (ref "S1") (pin "1") (pinfunction "1_1") (pintype "passive"))
      (node (ref "S1") (pin "2") (pinfunction "1_2") (pintype "passive"))
      (node (ref "U1") (pin "18") (pinfunction "GND_18") (pintype "bidirectional"))
      (node (ref "U1") (pin "35") (pinfunction "GND_35") (pintype "bidirectional"))
      (node (ref "U1") (pin "42") (pinfunction "GND_42") (pintype "bidirectional"))
      (node (ref "U1") (pin "5") (pinfunction "GNDANA_5") (pintype "bidirectional"))
      (node (ref "U2") (pin "2") (pinfunction "GND_2") (pintype "input"))
      (node (ref "U5") (pin "2") (pinfunction "V-_2") (pintype "power_in"))
      (node (ref "U6") (pin "2") (pinfunction "GND_2") (pintype "bidirectional"))
      (node (ref "U6") (pin "4") (pinfunction "GND_4") (pintype "bidirectional"))
      (node (ref "U6") (pin "6") (pinfunction "GND_6") (pintype "bidirectional"))
      (node (ref "U7") (pin "6") (pinfunction "GND_6") (pintype "bidirectional"))
    )
    (net (code "26") (name "ID") (class "Default")
      (node (ref "JP3") (pin "ID1") (pinfunction "USBID_ID1") (pintype "bidirectional"))
    )
    (net (code "27") (name "Net-(C19-Pad2)") (class "Default")
      (node (ref "C19") (pin "2") (pinfunction "2_2") (pintype "passive"))
      (node (ref "R12") (pin "2") (pinfunction "2_2") (pintype "passive"))
    )
    (net (code "28") (name "Net-(D1-PadC)") (class "Default")
      (node (ref "D1") (pin "C") (pinfunction "C_C") (pintype "passive"))
      (node (ref "R15") (pin "2") (pinfunction "2_2") (pintype "passive"))
    )
    (net (code "29") (name "Net-(D2-DO)") (class "Default")
      (node (ref "D2") (pin "2") (pinfunction "DO_2") (pintype "bidirectional"))
      (node (ref "D5") (pin "4") (pinfunction "DI_4") (pintype "bidirectional"))
    )
    (net (code "30") (name "Net-(D3-PadC)") (class "Default")
      (node (ref "D3") (pin "C") (pinfunction "C_C") (pintype "passive"))
      (node (ref "R17") (pin "2") (pinfunction "2_2") (pintype "passive"))
    )
    (net (code "31") (name "Net-(D4-PadC)") (class "Default")
      (node (ref "D4") (pin "C") (pinfunction "C_C") (pintype "passive"))
      (node (ref "R2") (pin "2") (pinfunction "2_2") (pintype "passive"))
    )
    (net (code "32") (name "Net-(D5-DO)") (class "Default")
      (node (ref "D5") (pin "2") (pinfunction "DO_2") (pintype "bidirectional"))
      (node (ref "D6") (pin "4") (pinfunction "DI_4") (pintype "bidirectional"))
    )
    (net (code "33") (name "Net-(D7-PadC)") (class "Default")
      (node (ref "D7") (pin "C") (pinfunction "C_C") (pintype "passive"))
      (node (ref "R6") (pin "2") (pinfunction "2_2") (pintype "passive"))
    )
    (net (code "34") (name "Net-(D31-DO)") (class "Default")
      (node (ref "D31") (pin "2") (pinfunction "DO_2") (pintype "bidirectional"))
      (node (ref "D32") (pin "4") (pinfunction "DI_4") (pintype "bidirectional"))
    )
    (net (code "35") (name "Net-(D32-DO)") (class "Default")
      (node (ref "D32") (pin "2") (pinfunction "DO_2") (pintype "bidirectional"))
      (node (ref "D33") (pin "4") (pinfunction "DI_4") (pintype "bidirectional"))
    )
    (net (code "36") (name "Net-(Q1-S)") (class "Default")
      (node (ref "D8") (pin "C") (pinfunction "C_C") (pintype "passive"))
      (node (ref "Q1") (pin "2") (pinfunction "S_2") (pintype "bidirectional"))
      (node (ref "S2") (pin "3") (pinfunction "S_3") (pintype "passive"))
    )
    (net (code "37") (name "Net-(U1-PA00(XIN32{slash}SER1:0{slash}TC2:0))") (class "Default")
      (node (ref "C5") (pin "2") (pinfunction "2_2") (pintype "passive"))
      (node (ref "U1") (pin "1") (pinfunction "PA00(XIN32/SER1:0/TC2:0)_1") (pintype "bidirectional"))
      (node (ref "Y1") (pin "P$2") (pinfunction "2_P$2") (pintype "passive"))
    )
    (net (code "38") (name "Net-(U1-PA01(XOUT32{slash}SER1:1{slash}TC2:1))") (class "Default")
      (node (ref "C6") (pin "1") (pinfunction "1_1") (pintype "passive"))
      (node (ref "U1") (pin "2") (pinfunction "PA01(XOUT32/SER1:1/TC2:1)_2") (pintype "bidirectional"))
      (node (ref "Y1") (pin "P$1") (pinfunction "1_P$1") (pintype "passive"))
    )
    (net (code "39") (name "Net-(U1-VDDCORE)") (class "Default")
      (node (ref "C2") (pin "1") (pinfunction "1_1") (pintype "passive"))
      (node (ref "U1") (pin "43") (pinfunction "VDDCORE_43") (pintype "bidirectional"))
    )
    (net (code "40") (name "Net-(U5-+IN)") (class "Default")
      (node (ref "C20") (pin "1") (pinfunction "1_1") (pintype "passive"))
      (node (ref "R11") (pin "2") (pinfunction "2_2") (pintype "passive"))
      (node (ref "R9") (pin "1") (pinfunction "1_1") (pintype "passive"))
      (node (ref "U5") (pin "3") (pinfunction "+IN_3") (pintype "input"))
    )
    (net (code "41") (name "Net-(U5--IN)") (class "Default")
      (node (ref "C17") (pin "1") (pinfunction "1_1") (pintype "passive"))
      (node (ref "R12") (pin "1") (pinfunction "1_1") (pintype "passive"))
      (node (ref "R13") (pin "2") (pinfunction "2_2") (pintype "passive"))
      (node (ref "U5") (pin "4") (pinfunction "-IN_4") (pintype "input"))
    )
    (net (code "42") (name "Net-(U6-OUT)") (class "Default")
      (node (ref "C19") (pin "1") (pinfunction "1_1") (pintype "passive"))
      (node (ref "U6") (pin "1") (pinfunction "OUT_1") (pintype "bidirectional"))
    )
    (net (code "43") (name "Net-(U7-LDR)") (class "Default")
      (node (ref "U7") (pin "3") (pinfunction "LDR_3") (pintype "bidirectional"))
      (node (ref "U7") (pin "4") (pinfunction "LEDK_4") (pintype "bidirectional"))
    )
    (net (code "44") (name "Net-(U7-LEDA)") (class "Default")
      (node (ref "C13") (pin "1") (pinfunction "1_1") (pintype "passive"))
      (node (ref "R29") (pin "1") (pinfunction "1_1") (pintype "passive"))
      (node (ref "U7") (pin "5") (pinfunction "LEDA_5") (pintype "bidirectional"))
    )
    (net (code "45") (name "SCL") (class "Default")
      (node (ref "J13") (pin "P$1") (pinfunction "1_P$1") (pintype "passive"))
      (node (ref "J15") (pin "P$1") (pinfunction "1_P$1") (pintype "passive"))
      (node (ref "J38") (pin "P$1") (pinfunction "1_P$1") (pintype "passive"))
      (node (ref "R5") (pin "2") (pinfunction "2_2") (pintype "passive"))
      (node (ref "U1") (pin "32") (pinfunction "PA23(I2C/SER3:0+)_32") (pintype "bidirectional"))
      (node (ref "U7") (pin "7") (pinfunction "SCL_7") (pintype "bidirectional"))
    )
    (net (code "46") (name "SDA") (class "Default")
      (node (ref "J12") (pin "P$1") (pinfunction "1_P$1") (pintype "passive"))
      (node (ref "J16") (pin "P$1") (pinfunction "1_P$1") (pintype "passive"))
      (node (ref "J39") (pin "P$1") (pinfunction "1_P$1") (pintype "passive"))
      (node (ref "R3") (pin "1") (pinfunction "1_1") (pintype "passive"))
      (node (ref "U1") (pin "31") (pinfunction "PA22(I2C/SER3:0+)_31") (pintype "bidirectional"))
      (node (ref "U7") (pin "1") (pinfunction "SDA_1") (pintype "bidirectional"))
    )
    (net (code "47") (name "SWCLK") (class "Default")
      (node (ref "JP5") (pin "4") (pinfunction "SWDCLK/TCK_4") (pintype "bidirectional"))
      (node (ref "U1") (pin "45") (pinfunction "PA30(SWCLK/SER1:2+)_45") (pintype "bidirectional"))
    )
    (net (code "48") (name "SWDIO") (class "Default")
      (node (ref "JP5") (pin "2") (pinfunction "SWDIO/TMS_2") (pintype "bidirectional"))
      (node (ref "U1") (pin "46") (pinfunction "PA31(SWDIO/SER1:3+)_46") (pintype "bidirectional"))
    )
    (net (code "49") (name "USB_D+") (class "Default")
      (node (ref "JP3") (pin "D+1") (pinfunction "D+_D+1") (pintype "bidirectional"))
      (node (ref "U1") (pin "34") (pinfunction "PA25(SER3:3+)_34") (pintype "bidirectional"))
    )
    (net (code "50") (name "USB_D-") (class "Default")
      (node (ref "JP3") (pin "D-1") (pinfunction "D-_D-1") (pintype "bidirectional"))
      (node (ref "U1") (pin "33") (pinfunction "PA24(SER3:2+)_33") (pintype "bidirectional"))
    )
    (net (code "51") (name "VIN") (class "Default")
      (node (ref "C9") (pin "1") (pinfunction "1_1") (pintype "passive"))
      (node (ref "J71") (pin "P$1") (pinfunction "1_P$1") (pintype "passive"))
      (node (ref "Q1") (pin "3") (pinfunction "D_3") (pintype "bidirectional"))
    )
    (net (code "52") (name "unconnected-(JP5-GNDDTCT-Pad9)") (class "Default")
      (node (ref "JP5") (pin "9") (pinfunction "GNDDTCT_9") (pintype "bidirectional"))
    )
    (net (code "53") (name "unconnected-(JP5-KEY-Pad7)") (class "Default")
      (node (ref "JP5") (pin "7") (pinfunction "KEY_7") (pintype "bidirectional"))
    )
    (net (code "54") (name "unconnected-(JP5-NC{slash}TDI-Pad8)") (class "Default")
      (node (ref "JP5") (pin "8") (pinfunction "NC/TDI_8") (pintype "bidirectional"))
    )
    (net (code "55") (name "unconnected-(JP5-SWO{slash}TDO-Pad6)") (class "Default")
      (node (ref "JP5") (pin "6") (pinfunction "SWO/TDO_6") (pintype "bidirectional"))
    )
    (net (code "56") (name "unconnected-(S2-O-Pad1)") (class "Default")
      (node (ref "S2") (pin "1") (pinfunction "O_1") (pintype "passive"))
    )
    (net (code "57") (name "unconnected-(U1-PA03(AIN1{slash}REFA)-Pad4)") (class "Default")
      (node (ref "U1") (pin "4") (pinfunction "PA03(AIN1/REFA)_4") (pintype "bidirectional"))
    )
    (net (code "58") (name "unconnected-(U1-PA05(AIN5{slash}SER0:1{slash}TC0:1)-Pad10)") (class "Default")
      (node (ref "U1") (pin "10") (pinfunction "PA05(AIN5/SER0:1/TC0:1)_10") (pintype "bidirectional"))
    )
    (net (code "59") (name "unconnected-(U1-PA12(I2C{slash}SER2:0+)-Pad21)") (class "Default")
      (node (ref "U1") (pin "21") (pinfunction "PA12(I2C/SER2:0+)_21") (pintype "bidirectional"))
    )
    (net (code "60") (name "unconnected-(U1-PA13(I2C{slash}SER2:1+)-Pad22)") (class "Default")
      (node (ref "U1") (pin "22") (pinfunction "PA13(I2C/SER2:1+)_22") (pintype "bidirectional"))
    )
    (net (code "61") (name "unconnected-(U1-PA27-Pad39)") (class "Default")
      (node (ref "U1") (pin "39") (pinfunction "PA27_39") (pintype "bidirectional"))
    )
    (net (code "62") (name "unconnected-(U1-PA28-Pad41)") (class "Default")
      (node (ref "U1") (pin "41") (pinfunction "PA28_41") (pintype "bidirectional"))
    )
    (net (code "63") (name "unconnected-(U1-PB02(AIN10{slash}SER5:0)-Pad47)") (class "Default")
      (node (ref "U1") (pin "47") (pinfunction "PB02(AIN10/SER5:0)_47") (pintype "bidirectional"))
    )
    (net (code "64") (name "unconnected-(U1-PB03(AIN11{slash}SER5:1)-Pad48)") (class "Default")
      (node (ref "U1") (pin "48") (pinfunction "PB03(AIN11/SER5:1)_48") (pintype "bidirectional"))
    )
    (net (code "65") (name "unconnected-(U1-PB10(SER4:2+)-Pad19)") (class "Default")
      (node (ref "U1") (pin "19") (pinfunction "PB10(SER4:2+)_19") (pintype "bidirectional"))
    )
    (net (code "66") (name "unconnected-(U1-PB11(SER4:3+)-Pad20)") (class "Default")
      (node (ref "U1") (pin "20") (pinfunction "PB11(SER4:3+)_20") (pintype "bidirectional"))
    )
    (net (code "67") (name "unconnected-(U1-PB22(SER5:2+)-Pad37)") (class "Default")
      (node (ref "U1") (pin "37") (pinfunction "PB22(SER5:2+)_37") (pintype "bidirectional"))
    )
    (net (code "68") (name "unconnected-(U1-PB23(SER5:3+)-Pad38)") (class "Default")
      (node (ref "U1") (pin "38") (pinfunction "PB23(SER5:3+)_38") (pintype "bidirectional"))
    )
    (net (code "69") (name "unconnected-(U2-NC-Pad4)") (class "Default")
      (node (ref "U2") (pin "4") (pinfunction "NC_4") (pintype "input"))
    )
    (net (code "70") (name "unconnected-(U7-INT-Pad2)") (class "Default")
      (node (ref "U7") (pin "2") (pinfunction "INT_2") (pintype "bidirectional"))
    )
  )
)
